# FMU_Power_FMU3_REV_C.net
KiCad netlist of a schematic drawn in Altium Designer
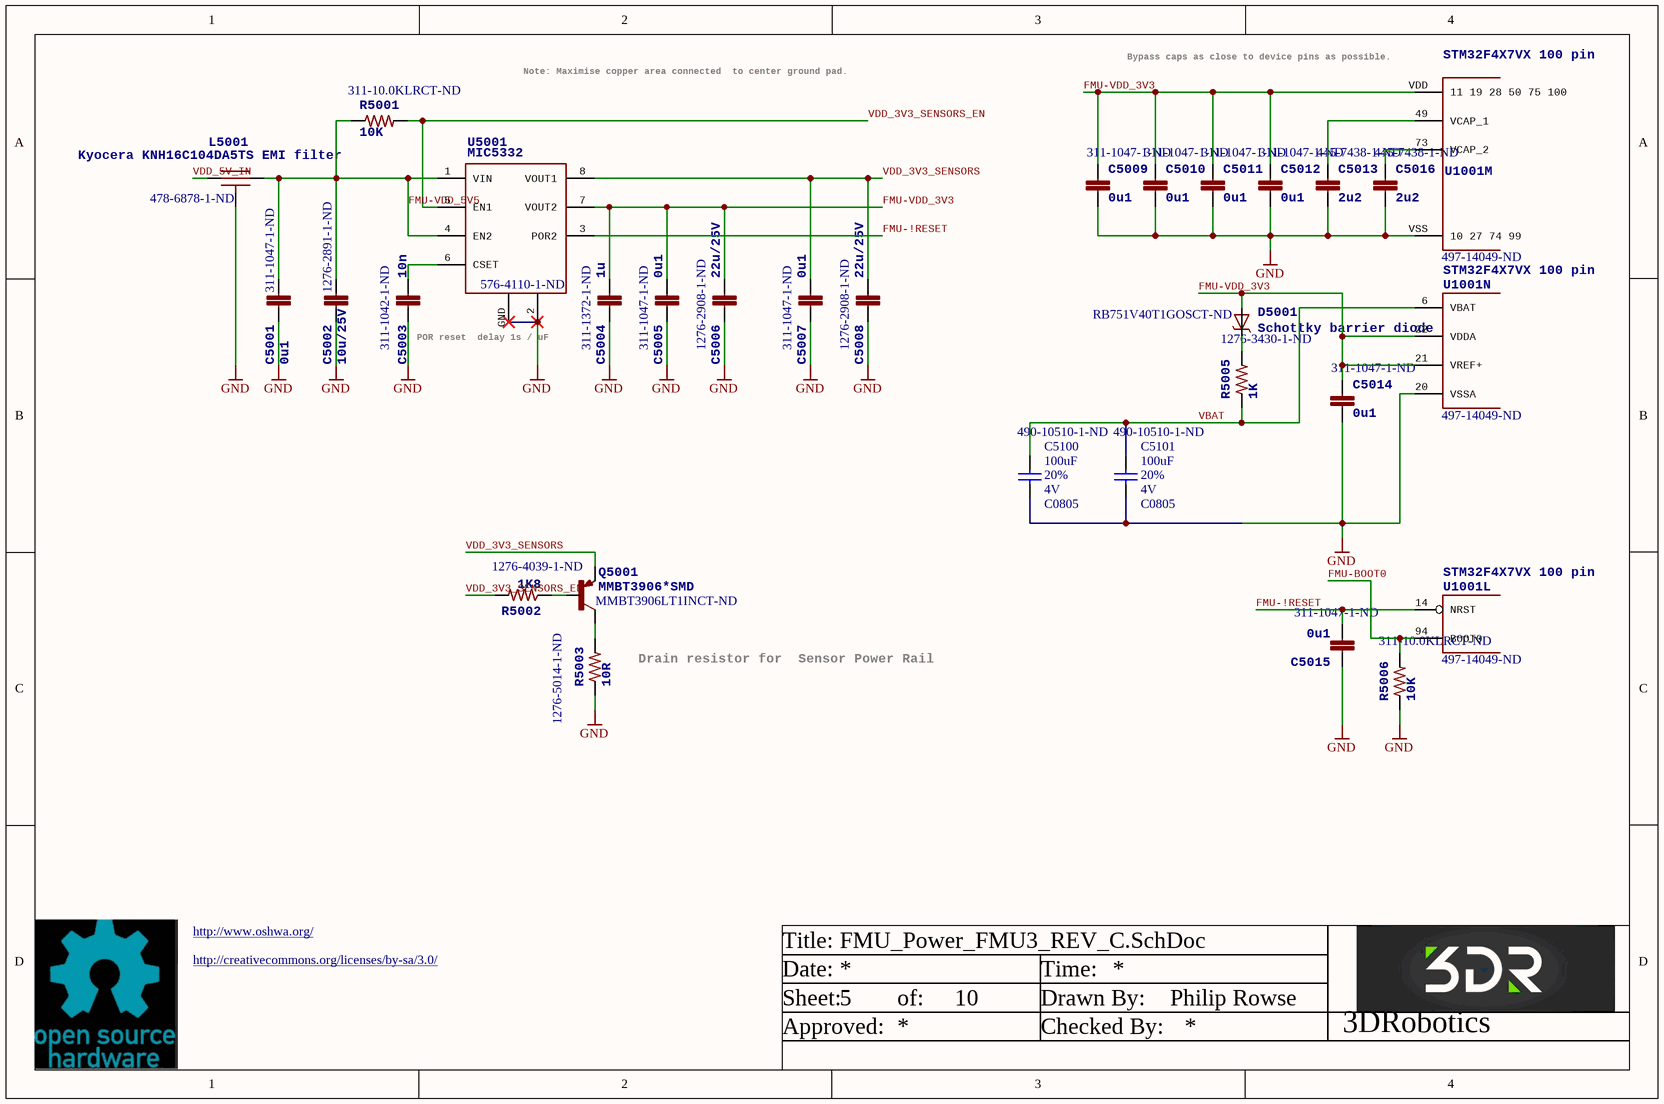
[diagram p0: FMU_Power_FMU3_REV_C.SchDoc]

(export (version "E")
  (design (tool "Eeschema 10.0.6"))
  (components
    (comp (ref "C5001")
      (value "0u1")
      (footprint "0402-CAP")
      (description "CAP CER 0.1UF 16V Y5V 0402")
      (fields
        (field (name "PARTNO") "CC0402ZRY5V7BB104")
        (field (name "SUPPLIER PART NUMBER 1") "311-1047-1-ND")
        (field (name "3DR_PARTNO") "ECM0700")
      )
      (libsource (lib "pixhawk2") (part "CAP0402"))
    )
    (comp (ref "C5002")
      (value "10u/25V")
      (footprint "0805-CAP")
      (description "CAP CER 10UF 25V 10% X5R 0805")
      (fields
        (field (name "PARTNO") "CL21A106KAYNNNE")
        (field (name "SUPPLIER PART NUMBER 1") "1276-2891-1-ND")
        (field (name "3DR_PARTNO") "ECM0714")
      )
      (libsource (lib "pixhawk2") (part "CAP0805"))
    )
    (comp (ref "C5003")
      (value "10n")
      (footprint "0402-CAP")
      (description "CAP CER 10000PF 16V 10% X7R 0402")
      (fields
        (field (name "PARTNO") "CC0402KRX7R7BB103")
        (field (name "SUPPLIER PART NUMBER 1") "311-1042-1-ND")
        (field (name "3DR_PARTNO") "ECM0711")
      )
      (libsource (lib "") (part "CAP0402_1"))
    )
    (comp (ref "C5004")
      (value "1u")
      (footprint "0603-CAP")
      (description "CAP CER 1UF 16V Y5V 0603")
      (fields
        (field (name "PARTNO") "CC0603ZRY5V7BB105")
        (field (name "SUPPLIER PART NUMBER 1") "311-1372-1-ND")
        (field (name "3DR_PARTNO") "ECM0705")
      )
      (libsource (lib "pixhawk2") (part "CAP0603"))
    )
    (comp (ref "C5005")
      (value "0u1")
      (footprint "0402-CAP")
      (description "CAP CER 0.1UF 16V Y5V 0402")
      (fields
        (field (name "PARTNO") "CC0402ZRY5V7BB104")
        (field (name "SUPPLIER PART NUMBER 1") "311-1047-1-ND")
        (field (name "3DR_PARTNO") "ECM0700")
      )
      (libsource (lib "pixhawk2") (part "CAP0402"))
    )
    (comp (ref "C5006")
      (value "22u/25V")
      (footprint "0805-CAP")
      (description "CAP CER 22UF 25V 20% X5R 0805")
      (fields
        (field (name "PARTNO") "CL21A226MAQNNNE")
        (field (name "SUPPLIER PART NUMBER 1") "1276-2908-1-ND")
        (field (name "3DR_PARTNO") "ECM0715")
      )
      (libsource (lib "pixhawk2") (part "CAP0805"))
    )
    (comp (ref "C5007")
      (value "0u1")
      (footprint "0402-CAP")
      (description "CAP CER 0.1UF 16V Y5V 0402")
      (fields
        (field (name "PARTNO") "CC0402ZRY5V7BB104")
        (field (name "SUPPLIER PART NUMBER 1") "311-1047-1-ND")
        (field (name "3DR_PARTNO") "ECM0700")
      )
      (libsource (lib "pixhawk2") (part "CAP0402"))
    )
    (comp (ref "C5008")
      (value "22u/25V")
      (footprint "0805-CAP")
      (description "CAP CER 22UF 25V 20% X5R 0805")
      (fields
        (field (name "PARTNO") "CL21A226MAQNNNE")
        (field (name "SUPPLIER PART NUMBER 1") "1276-2908-1-ND")
        (field (name "3DR_PARTNO") "ECM0715")
      )
      (libsource (lib "pixhawk2") (part "CAP0805"))
    )
    (comp (ref "C5009")
      (value "0u1")
      (footprint "0402-CAP")
      (description "CAP CER 0.1UF 16V Y5V 0402")
      (fields
        (field (name "PARTNO") "CC0402ZRY5V7BB104")
        (field (name "SUPPLIER PART NUMBER 1") "311-1047-1-ND")
        (field (name "3DR_PARTNO") "ECM0700")
      )
      (libsource (lib "pixhawk2") (part "CAP0402"))
    )
    (comp (ref "C5010")
      (value "0u1")
      (footprint "0402-CAP")
      (description "CAP CER 0.1UF 16V Y5V 0402")
      (fields
        (field (name "PARTNO") "CC0402ZRY5V7BB104")
        (field (name "SUPPLIER PART NUMBER 1") "311-1047-1-ND")
        (field (name "3DR_PARTNO") "ECM0700")
      )
      (libsource (lib "pixhawk2") (part "CAP0402"))
    )
    (comp (ref "C5011")
      (value "0u1")
      (footprint "0402-CAP")
      (description "CAP CER 0.1UF 16V Y5V 0402")
      (fields
        (field (name "PARTNO") "CC0402ZRY5V7BB104")
        (field (name "SUPPLIER PART NUMBER 1") "311-1047-1-ND")
        (field (name "3DR_PARTNO") "ECM0700")
      )
      (libsource (lib "pixhawk2") (part "CAP0402"))
    )
    (comp (ref "C5012")
      (value "0u1")
      (footprint "0402-CAP")
      (description "CAP CER 0.1UF 16V Y5V 0402")
      (fields
        (field (name "PARTNO") "CC0402ZRY5V7BB104")
        (field (name "SUPPLIER PART NUMBER 1") "311-1047-1-ND")
        (field (name "3DR_PARTNO") "ECM0700")
      )
      (libsource (lib "pixhawk2") (part "CAP0402"))
    )
    (comp (ref "C5013")
      (value "2u2")
      (footprint "0603-CAP")
      (description "CAP CER 2.2UF 16V 10% X6S 0603")
      (fields
        (field (name "PARTNO") "C1608X6S1C225K080AC")
        (field (name "SUPPLIER PART NUMBER 1") "445-7438-1-ND")
        (field (name "3DR_PARTNO") "ECM0619")
      )
      (libsource (lib "pixhawk2") (part "CAP0603"))
    )
    (comp (ref "C5014")
      (value "0u1")
      (footprint "0402-CAP")
      (description "CAP CER 0.1UF 16V Y5V 0402")
      (fields
        (field (name "PARTNO") "CC0402ZRY5V7BB104")
        (field (name "SUPPLIER PART NUMBER 1") "311-1047-1-ND")
        (field (name "3DR_PARTNO") "ECM0700")
      )
      (libsource (lib "pixhawk2") (part "CAP0402"))
    )
    (comp (ref "C5015")
      (value "0u1")
      (footprint "0402-CAP")
      (description "CAP CER 0.1UF 16V Y5V 0402")
      (fields
        (field (name "PARTNO") "CC0402ZRY5V7BB104")
        (field (name "SUPPLIER PART NUMBER 1") "311-1047-1-ND")
        (field (name "3DR_PARTNO") "ECM0700")
      )
      (libsource (lib "") (part "CAP0402_2"))
    )
    (comp (ref "C5016")
      (value "2u2")
      (footprint "0603-CAP")
      (description "CAP CER 2.2UF 16V 10% X6S 0603")
      (fields
        (field (name "PARTNO") "C1608X6S1C225K080AC")
        (field (name "SUPPLIER PART NUMBER 1") "445-7438-1-ND")
        (field (name "3DR_PARTNO") "ECM0619")
      )
      (libsource (lib "pixhawk2") (part "CAP0603"))
    )
    (comp (ref "C5100")
      (value "100uF")
      (footprint "C0805")
      (fields
        (field (name "TOLERANCE") "20%")
        (field (name "VOLTAGE") "4V")
        (field (name "SUPPLIER PART NUMBER 1") "490-10510-1-ND")
        (field (name "Comment") "GRM21BR60G107ME15L")
      )
      (libsource (lib "3DR") (part "Capacitor"))
    )
    (comp (ref "C5101")
      (value "100uF")
      (footprint "C0805")
      (fields
        (field (name "TOLERANCE") "20%")
        (field (name "VOLTAGE") "4V")
        (field (name "SUPPLIER PART NUMBER 1") "490-10510-1-ND")
        (field (name "Comment") "GRM21BR60G107ME15L")
      )
      (libsource (lib "3DR") (part "Capacitor"))
    )
    (comp (ref "D5001")
      (value "Schottky barrier diode")
      (footprint "SOD323")
      (description "DIODE SCHOTTKY 30V 0.03A SOD323")
      (fields
        (field (name "SUPPLIER PART NUMBER 1") "RB751V40T1GOSCT-ND")
        (field (name "3DR_PARTNO") "ECM0839")
        (field (name "PARTNO") "RB751V40T1G")
      )
      (libsource (lib "pixhawk2") (part "DIODE-SCHOTTKY_SOD323"))
    )
    (comp (ref "L5001")
      (value "Kyocera KNH16C104DA5TS EMI filter")
      (footprint "KYOCERA-KNH16-DA")
      (description "FILTER CAP 0.1UF 2A 25V 0603")
      (fields
        (field (name "SUPPLIER PART NUMBER 1") "478-6878-1-ND")
        (field (name "3DR_PARTNO") "ECM0719")
        (field (name "PARTNO") "KNH16C104DA5TS")
      )
      (libsource (lib "pixhawk2") (part "KNH16C104DA5TS"))
    )
    (comp (ref "Q5001")
      (value "MMBT3906*SMD")
      (footprint "SOT23-BEC")
      (description "TRANSISTOR SWITCHING PNP SOT-23")
      (fields
        (field (name "SUPPLIER PART NUMBER 1") "MMBT3906LT1INCT-ND")
        (field (name "3DR_PARTNO") "ECM0833")
        (field (name "PARTNO") "MMBT 3906 LT1")
      )
      (libsource (lib "transistor-pnp") (part "MMBT3906*SMD"))
    )
    (comp (ref "R5001")
      (value "10K")
      (footprint "0402-RES")
      (description "RES 10K OHM 1/16W 1% 0402 SMD")
      (fields
        (field (name "PARTNO") "RC0402FR-0710KL")
        (field (name "SUPPLIER PART NUMBER 1") "311-10.0KLRCT-ND")
        (field (name "3DR_PARTNO") "ECM0800")
      )
      (libsource (lib "pixhawk2") (part "RESISTOR0402-RES"))
    )
    (comp (ref "R5002")
      (value "1K8")
      (footprint "0402-RES")
      (description "RES 1.8K OHM 1/16W 1% 0402")
      (fields
        (field (name "PARTNO") "RC1005F182CS")
        (field (name "SUPPLIER PART NUMBER 1") "1276-4039-1-ND")
        (field (name "3DR_PARTNO") "ECM0807")
      )
      (libsource (lib "pixhawk2") (part "RESISTOR0402-RES"))
    )
    (comp (ref "R5003")
      (value "10R")
      (footprint "0603-RES")
      (description "RES 10 OHM 1/10W 5% 0603")
      (fields
        (field (name "PARTNO") "RC1608J100CS")
        (field (name "SUPPLIER PART NUMBER 1") "1276-5014-1-ND")
        (field (name "3DR_PARTNO") "ECM0811")
      )
      (libsource (lib "pixhawk2") (part "RESISTOR0603-RES"))
    )
    (comp (ref "R5005")
      (value "1K")
      (footprint "0402-RES")
      (description "RES 1K OHM 1/16W 1% 0402")
      (fields
        (field (name "PARTNO") "RC1005F102CS")
        (field (name "SUPPLIER PART NUMBER 1") "1276-3430-1-ND")
        (field (name "3DR_PARTNO") "ECM0804")
      )
      (libsource (lib "pixhawk2") (part "RESISTOR0402-RES"))
    )
    (comp (ref "R5006")
      (value "10K")
      (footprint "0402-RES")
      (description "RES 10K OHM 1/16W 1% 0402 SMD")
      (fields
        (field (name "PARTNO") "RC0402FR-0710KL")
        (field (name "SUPPLIER PART NUMBER 1") "311-10.0KLRCT-ND")
        (field (name "3DR_PARTNO") "ECM0800")
      )
      (libsource (lib "pixhawk2") (part "RESISTOR0402-RES"))
    )
    (comp (ref "U1001")
      (value "STM32F4X7VX 100 pin")
      (footprint "TQFP100")
      (description "REV 3 Silicon or later IC MCU ARM 2MB FLASH 100LQFP")
      (fields (field (name "SUPPLIER PART NUMBER 1") "497-14049-ND") (field (name "3DR_PARTNO") "ECM0841"))
      (libsource (lib "pixhawk2") (part "STM32F4X7VX"))
    )
    (comp (ref "U5001")
      (value "MIC5332")
      (footprint "MLF-8-EPAD")
      (description "IC REG LDO 3.3V 0.3A 8TMLF")
      (fields
        (field (name "SUPPLIER PART NUMBER 1") "576-4110-1-ND")
        (field (name "3DR_PARTNO") "ECM0832")
        (field (name "PARTNO") "MIC5332-SSYMT TR")
      )
      (libsource (lib "pixhawk2") (part "MIC5332"))
    )
  )
  (nets
    (net (code "1") (name "/FMU-!RESET") (class "Default")
      (node (ref "C5015") (pin "P$2") (pinfunction "2_P$2") (pintype "passive"))
      (node (ref "U1001") (pin "14") (pinfunction "NRST_14") (pintype "passive"))
      (node (ref "U5001") (pin "3") (pinfunction "POR2_3") (pintype "passive"))
    )
    (net (code "2") (name "/FMU-BOOT0") (class "Default")
      (node (ref "R5006") (pin "P$2") (pinfunction "2_P$2") (pintype "passive"))
      (node (ref "U1001") (pin "94") (pinfunction "BOOT0_94") (pintype "passive"))
    )
    (net (code "3") (name "/FMU-VDD_3V3") (class "Default")
      (node (ref "C5004") (pin "P$1") (pinfunction "1_P$1") (pintype "passive"))
      (node (ref "C5005") (pin "P$1") (pinfunction "1_P$1") (pintype "passive"))
      (node (ref "C5006") (pin "P$1") (pinfunction "1_P$1") (pintype "passive"))
      (node (ref "C5009") (pin "P$1") (pinfunction "1_P$1") (pintype "passive"))
      (node (ref "C5010") (pin "P$1") (pinfunction "1_P$1") (pintype "passive"))
      (node (ref "C5011") (pin "P$1") (pinfunction "1_P$1") (pintype "passive"))
      (node (ref "C5012") (pin "P$1") (pinfunction "1_P$1") (pintype "passive"))
      (node (ref "C5014") (pin "P$1") (pinfunction "1_P$1") (pintype "passive"))
      (node (ref "D5001") (pin "A") (pinfunction "A_A") (pintype "passive"))
      (node (ref "U1001") (pin "21") (pinfunction "VREF+_21") (pintype "passive"))
      (node (ref "U1001") (pin "22") (pinfunction "VDDA_22") (pintype "power_in"))
      (node (ref "U1001") (pin "VDD") (pinfunction "11_19_28_50_75_100_VDD") (pintype "power_in"))
      (node (ref "U5001") (pin "7") (pinfunction "VOUT2_7") (pintype "passive"))
    )
    (net (code "4") (name "/FMU-VDD_5V5") (class "Default")
      (node (ref "C5001") (pin "P$1") (pinfunction "1_P$1") (pintype "passive"))
      (node (ref "C5002") (pin "P$1") (pinfunction "1_P$1") (pintype "passive"))
      (node (ref "L5001") (pin "P$2") (pinfunction "P$2_P$2") (pintype "passive"))
      (node (ref "R5001") (pin "P$1") (pinfunction "1_P$1") (pintype "passive"))
      (node (ref "U5001") (pin "1") (pinfunction "VIN_1") (pintype "passive"))
      (node (ref "U5001") (pin "4") (pinfunction "EN2_4") (pintype "passive"))
    )
    (net (code "5") (name "/VBAT") (class "Default")
      (node (ref "C5100") (pin "2") (pinfunction "2_2") (pintype "passive"))
      (node (ref "C5101") (pin "2") (pinfunction "2_2") (pintype "passive"))
      (node (ref "R5005") (pin "P$1") (pinfunction "1_P$1") (pintype "passive"))
      (node (ref "U1001") (pin "6") (pinfunction "VBAT_6") (pintype "power_in"))
    )
    (net (code "6") (name "/VDD_3V3_SENSORS") (class "Default")
      (node (ref "C5007") (pin "P$1") (pinfunction "1_P$1") (pintype "passive"))
      (node (ref "C5008") (pin "P$1") (pinfunction "1_P$1") (pintype "passive"))
      (node (ref "Q5001") (pin "E") (pinfunction "E_E") (pintype "passive"))
      (node (ref "U5001") (pin "8") (pinfunction "VOUT1_8") (pintype "passive"))
    )
    (net (code "7") (name "/VDD_3V3_SENSORS_EN") (class "Default")
      (node (ref "R5001") (pin "P$2") (pinfunction "2_P$2") (pintype "passive"))
      (node (ref "R5002") (pin "P$2") (pinfunction "2_P$2") (pintype "passive"))
      (node (ref "U5001") (pin "5") (pinfunction "EN1_5") (pintype "passive"))
    )
    (net (code "8") (name "/VDD_5V_IN") (class "Default")
      (node (ref "L5001") (pin "P$1") (pinfunction "P$1_P$1") (pintype "passive"))
    )
    (net (code "9") (name "GND") (class "Default")
      (node (ref "C5001") (pin "P$2") (pinfunction "2_P$2") (pintype "passive"))
      (node (ref "C5002") (pin "P$2") (pinfunction "2_P$2") (pintype "passive"))
      (node (ref "C5003") (pin "P$1") (pinfunction "1_P$1") (pintype "passive"))
      (node (ref "C5004") (pin "P$2") (pinfunction "2_P$2") (pintype "passive"))
      (node (ref "C5005") (pin "P$2") (pinfunction "2_P$2") (pintype "passive"))
      (node (ref "C5006") (pin "P$2") (pinfunction "2_P$2") (pintype "passive"))
      (node (ref "C5007") (pin "P$2") (pinfunction "2_P$2") (pintype "passive"))
      (node (ref "C5008") (pin "P$2") (pinfunction "2_P$2") (pintype "passive"))
      (node (ref "C5009") (pin "P$2") (pinfunction "2_P$2") (pintype "passive"))
      (node (ref "C5010") (pin "P$2") (pinfunction "2_P$2") (pintype "passive"))
      (node (ref "C5011") (pin "P$2") (pinfunction "2_P$2") (pintype "passive"))
      (node (ref "C5012") (pin "P$2") (pinfunction "2_P$2") (pintype "passive"))
      (node (ref "C5013") (pin "P$2") (pinfunction "2_P$2") (pintype "passive"))
      (node (ref "C5014") (pin "P$2") (pinfunction "2_P$2") (pintype "passive"))
      (node (ref "C5015") (pin "P$1") (pinfunction "1_P$1") (pintype "passive"))
      (node (ref "C5016") (pin "P$2") (pinfunction "2_P$2") (pintype "passive"))
      (node (ref "C5100") (pin "1") (pinfunction "1_1") (pintype "passive"))
      (node (ref "C5101") (pin "1") (pinfunction "1_1") (pintype "passive"))
      (node (ref "L5001") (pin "GND") (pinfunction "GND_GND") (pintype "passive"))
      (node (ref "R5003") (pin "1") (pinfunction "1_1") (pintype "passive"))
      (node (ref "R5006") (pin "P$1") (pinfunction "1_P$1") (pintype "passive"))
      (node (ref "U1001") (pin "20") (pinfunction "VSSA_20") (pintype "power_in"))
      (node (ref "U1001") (pin "VSS") (pinfunction "10_27_74_99_VSS") (pintype "power_in"))
      (node (ref "U5001") (pin "2") (pinfunction "GND_2") (pintype "power_in"))
      (node (ref "U5001") (pin "GND") (pinfunction "GND_GND") (pintype "power_in"))
    )
    (net (code "10") (name "Net-(C5003-2)") (class "Default")
      (node (ref "C5003") (pin "P$2") (pinfunction "2_P$2") (pintype "passive"))
      (node (ref "U5001") (pin "6") (pinfunction "CSET_6") (pintype "passive"))
    )
    (net (code "11") (name "Net-(C5013-1)") (class "Default")
      (node (ref "C5013") (pin "P$1") (pinfunction "1_P$1") (pintype "passive"))
      (node (ref "U1001") (pin "49") (pinfunction "VCAP_1_49") (pintype "power_in"))
    )
    (net (code "12") (name "Net-(C5016-1)") (class "Default")
      (node (ref "C5016") (pin "P$1") (pinfunction "1_P$1") (pintype "passive"))
      (node (ref "U1001") (pin "73") (pinfunction "VCAP_2_73") (pintype "power_in"))
    )
    (net (code "13") (name "Net-(Q5001-PadC)") (class "Default")
      (node (ref "Q5001") (pin "C") (pinfunction "C_C") (pintype "passive"))
      (node (ref "R5003") (pin "2") (pinfunction "2_2") (pintype "passive"))
    )
    (net (code "14") (name "Net-(R5002-1)") (class "Default")
      (node (ref "Q5001") (pin "B") (pinfunction "B_B") (pintype "passive"))
      (node (ref "R5002") (pin "P$1") (pinfunction "1_P$1") (pintype "passive"))
    )
    (net (code "15") (name "Net-(R5005-2)") (class "Default")
      (node (ref "D5001") (pin "C") (pinfunction "C_C") (pintype "passive"))
      (node (ref "R5005") (pin "P$2") (pinfunction "2_P$2") (pintype "passive"))
    )
  )
)
